# mobo_v2_0_6-20-18-mobo-only.net
KiCad netlist of a schematic drawn in EAGLE
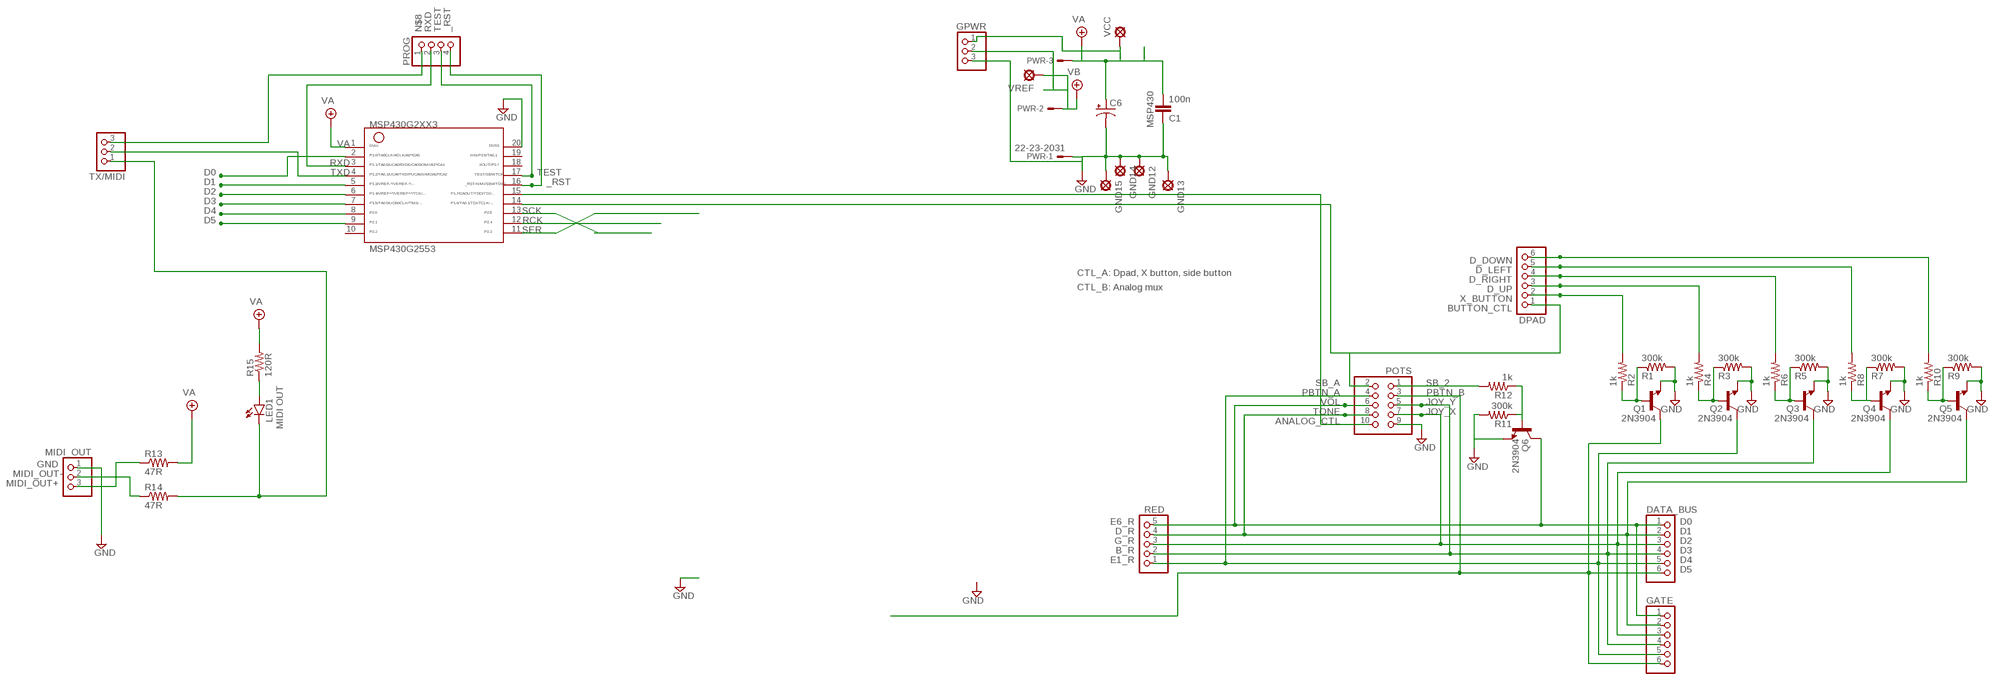
[diagram p0: schematic, sheet 1]

(export (version "E")
  (design (tool "Eeschema 10.0.6"))
  (components
    (comp (ref "C1")
      (value "100n")
      (footprint "eagle-import:050X030_050_3")
      (libsource (lib "eagle-import") (part "050X030_050"))
    )
    (comp (ref "C6")
      (value "0501")
      (footprint "eagle-import:050_020_1")
      (libsource (lib "eagle-import") (part "0501"))
    )
    (comp (ref "DATA_BUS")
      (value "PINHD-1X6")
      (footprint "eagle-import:1X06")
      (libsource (lib "eagle-import") (part "PINHD-1X6"))
    )
    (comp (ref "DPAD")
      (value "PINHD-1X6")
      (footprint "eagle-import:1X06")
      (libsource (lib "eagle-import") (part "PINHD-1X6"))
    )
    (comp (ref "GATE")
      (value "PINHD-1X6")
      (footprint "eagle-import:1X06")
      (libsource (lib "eagle-import") (part "PINHD-1X6"))
    )
    (comp (ref "GND12")
      (value "PAD")
      (footprint "eagle-import:SQUARE")
      (libsource (lib "eagle-import") (part "PAD"))
    )
    (comp (ref "GND13")
      (value "PAD")
      (footprint "eagle-import:SQUARE")
      (libsource (lib "eagle-import") (part "PAD"))
    )
    (comp (ref "GND14")
      (value "PAD")
      (footprint "eagle-import:SQUARE")
      (libsource (lib "eagle-import") (part "PAD"))
    )
    (comp (ref "GND15")
      (value "PAD")
      (footprint "eagle-import:SQUARE")
      (libsource (lib "eagle-import") (part "PAD"))
    )
    (comp (ref "GPWR")
      (value "PINHD-1X3")
      (footprint "eagle-import:1X03")
      (libsource (lib "eagle-import") (part "PINHD-1X3"))
    )
    (comp (ref "LED1")
      (value "LED3MM")
      (footprint "eagle-import:LED3MM")
      (libsource (lib "eagle-import") (part "LED3MM"))
    )
    (comp (ref "MIDI_OUT")
      (value "PINHD-1X3")
      (footprint "eagle-import:1X03")
      (libsource (lib "eagle-import") (part "PINHD-1X3"))
    )
    (comp (ref "MSP430G2553")
      (value "G2XX3---N20")
      (footprint "eagle-import:N20")
      (libsource (lib "eagle-import") (part "G2XX3---N20"))
    )
    (comp (ref "POTS")
      (value "PINHD-2X5IDC")
      (footprint "eagle-import:10PIN_IDC")
      (libsource (lib "eagle-import") (part "PINHD-2X5IDC"))
    )
    (comp (ref "PROG")
      (value "PINHD-1X4")
      (footprint "eagle-import:1X04")
      (libsource (lib "eagle-import") (part "PINHD-1X4"))
    )
    (comp (ref "PWR")
      (value "22-23-2031")
      (footprint "eagle-import:22-23-2031")
      (fields (field (name "MF") "MOLEX"))
      (libsource (lib "eagle-import") (part "22-23-2031"))
    )
    (comp (ref "Q1")
      (value "2N3904")
      (footprint "eagle-import:TO92-")
      (libsource (lib "eagle-import") (part "2N3904"))
    )
    (comp (ref "Q2")
      (value "2N3904")
      (footprint "eagle-import:TO92-")
      (libsource (lib "eagle-import") (part "2N3904"))
    )
    (comp (ref "Q3")
      (value "2N3904")
      (footprint "eagle-import:TO92-")
      (libsource (lib "eagle-import") (part "2N3904"))
    )
    (comp (ref "Q4")
      (value "2N3904")
      (footprint "eagle-import:TO92-")
      (libsource (lib "eagle-import") (part "2N3904"))
    )
    (comp (ref "Q5")
      (value "2N3904")
      (footprint "eagle-import:TO92-")
      (libsource (lib "eagle-import") (part "2N3904"))
    )
    (comp (ref "Q6")
      (value "2N3904")
      (footprint "eagle-import:TO92-")
      (libsource (lib "eagle-import") (part "2N3904"))
    )
    (comp (ref "R1")
      (value "300k")
      (footprint "eagle-import:R0207_3")
      (libsource (lib "eagle-import") (part "6MM.3"))
    )
    (comp (ref "R2")
      (value "1k")
      (footprint "eagle-import:R0207_3")
      (libsource (lib "eagle-import") (part "6MM.3"))
    )
    (comp (ref "R3")
      (value "300k")
      (footprint "eagle-import:R0207_3")
      (libsource (lib "eagle-import") (part "6MM.3"))
    )
    (comp (ref "R4")
      (value "1k")
      (footprint "eagle-import:R0207_3")
      (libsource (lib "eagle-import") (part "6MM.3"))
    )
    (comp (ref "R5")
      (value "300k")
      (footprint "eagle-import:R0207_3")
      (libsource (lib "eagle-import") (part "6MM.3"))
    )
    (comp (ref "R6")
      (value "1k")
      (footprint "eagle-import:R0207_3")
      (libsource (lib "eagle-import") (part "6MM.3"))
    )
    (comp (ref "R7")
      (value "300k")
      (footprint "eagle-import:R0207_3")
      (libsource (lib "eagle-import") (part "6MM.3"))
    )
    (comp (ref "R8")
      (value "1k")
      (footprint "eagle-import:R0207_3")
      (libsource (lib "eagle-import") (part "6MM.3"))
    )
    (comp (ref "R9")
      (value "300k")
      (footprint "eagle-import:R0207_3")
      (libsource (lib "eagle-import") (part "6MM.3"))
    )
    (comp (ref "R10")
      (value "1k")
      (footprint "eagle-import:R0207_3")
      (libsource (lib "eagle-import") (part "6MM.3"))
    )
    (comp (ref "R11")
      (value "300k")
      (footprint "eagle-import:R0207_3")
      (libsource (lib "eagle-import") (part "6MM.3"))
    )
    (comp (ref "R12")
      (value "1k")
      (footprint "eagle-import:R0207_3")
      (libsource (lib "eagle-import") (part "6MM.3"))
    )
    (comp (ref "R13")
      (value "47R")
      (footprint "eagle-import:R0207_3")
      (libsource (lib "eagle-import") (part "6MM.3"))
    )
    (comp (ref "R14")
      (value "47R")
      (footprint "eagle-import:R0207_3")
      (libsource (lib "eagle-import") (part "6MM.3"))
    )
    (comp (ref "R15")
      (value "120R")
      (footprint "eagle-import:R0207_3")
      (libsource (lib "eagle-import") (part "6MM.3"))
    )
    (comp (ref "RED")
      (value "PINHD-1X5")
      (footprint "eagle-import:1X05")
      (libsource (lib "eagle-import") (part "PINHD-1X5"))
    )
    (comp (ref "TX/MIDI")
      (value "PINHD-1X3")
      (footprint "eagle-import:1X03")
      (libsource (lib "eagle-import") (part "PINHD-1X3"))
    )
    (comp (ref "VCC")
      (value "PAD")
      (footprint "eagle-import:SQUARE")
      (libsource (lib "eagle-import") (part "PAD"))
    )
    (comp (ref "VREF")
      (value "PAD")
      (footprint "eagle-import:SQUARE")
      (libsource (lib "eagle-import") (part "PAD"))
    )
  )
  (nets
    (net (code "1") (name "/ANALOG_CTL") (class "Default")
      (node (ref "MSP430G2553") (pin "15") (pinfunction "15_15") (pintype "bidirectional"))
      (node (ref "POTS") (pin "10") (pinfunction "10_10") (pintype "passive"))
    )
    (net (code "2") (name "/BUTTON_CTL") (class "Default")
      (node (ref "DPAD") (pin "1") (pinfunction "1_1") (pintype "passive"))
      (node (ref "MSP430G2553") (pin "14") (pinfunction "14_14") (pintype "bidirectional"))
      (node (ref "POTS") (pin "2") (pinfunction "2_2") (pintype "passive"))
    )
    (net (code "3") (name "/D0") (class "Default")
      (node (ref "DATA_BUS") (pin "1") (pinfunction "1_1") (pintype "passive"))
      (node (ref "GATE") (pin "1") (pinfunction "1_1") (pintype "passive"))
      (node (ref "MSP430G2553") (pin "2") (pinfunction "2_2") (pintype "bidirectional"))
      (node (ref "POTS") (pin "6") (pinfunction "6_6") (pintype "passive"))
      (node (ref "Q6") (pin "1") (pinfunction "C_1") (pintype "passive"))
      (node (ref "RED") (pin "5") (pinfunction "5_5") (pintype "passive"))
    )
    (net (code "4") (name "/D1") (class "Default")
      (node (ref "DATA_BUS") (pin "2") (pinfunction "2_2") (pintype "passive"))
      (node (ref "GATE") (pin "2") (pinfunction "2_2") (pintype "passive"))
      (node (ref "MSP430G2553") (pin "5") (pinfunction "5_5") (pintype "bidirectional"))
      (node (ref "POTS") (pin "8") (pinfunction "8_8") (pintype "passive"))
      (node (ref "Q5") (pin "1") (pinfunction "C_1") (pintype "passive"))
      (node (ref "RED") (pin "4") (pinfunction "4_4") (pintype "passive"))
    )
    (net (code "5") (name "/D2") (class "Default")
      (node (ref "DATA_BUS") (pin "3") (pinfunction "3_3") (pintype "passive"))
      (node (ref "GATE") (pin "3") (pinfunction "3_3") (pintype "passive"))
      (node (ref "MSP430G2553") (pin "6") (pinfunction "6_6") (pintype "bidirectional"))
      (node (ref "POTS") (pin "7") (pinfunction "7_7") (pintype "passive"))
      (node (ref "Q4") (pin "1") (pinfunction "C_1") (pintype "passive"))
      (node (ref "RED") (pin "3") (pinfunction "3_3") (pintype "passive"))
    )
    (net (code "6") (name "/D3") (class "Default")
      (node (ref "DATA_BUS") (pin "4") (pinfunction "4_4") (pintype "passive"))
      (node (ref "GATE") (pin "4") (pinfunction "4_4") (pintype "passive"))
      (node (ref "MSP430G2553") (pin "7") (pinfunction "7_7") (pintype "bidirectional"))
      (node (ref "POTS") (pin "5") (pinfunction "5_5") (pintype "passive"))
      (node (ref "Q3") (pin "1") (pinfunction "C_1") (pintype "passive"))
      (node (ref "RED") (pin "2") (pinfunction "2_2") (pintype "passive"))
    )
    (net (code "7") (name "/D4") (class "Default")
      (node (ref "DATA_BUS") (pin "5") (pinfunction "5_5") (pintype "passive"))
      (node (ref "GATE") (pin "5") (pinfunction "5_5") (pintype "passive"))
      (node (ref "MSP430G2553") (pin "8") (pinfunction "8_8") (pintype "bidirectional"))
      (node (ref "POTS") (pin "4") (pinfunction "4_4") (pintype "passive"))
      (node (ref "Q2") (pin "1") (pinfunction "C_1") (pintype "passive"))
      (node (ref "RED") (pin "1") (pinfunction "1_1") (pintype "passive"))
    )
    (net (code "8") (name "/D5") (class "Default")
      (node (ref "DATA_BUS") (pin "6") (pinfunction "6_6") (pintype "passive"))
      (node (ref "GATE") (pin "6") (pinfunction "6_6") (pintype "passive"))
      (node (ref "MSP430G2553") (pin "9") (pinfunction "9_9") (pintype "bidirectional"))
      (node (ref "POTS") (pin "3") (pinfunction "3_3") (pintype "passive"))
      (node (ref "Q1") (pin "1") (pinfunction "C_1") (pintype "passive"))
    )
    (net (code "9") (name "/D_DOWN") (class "Default")
      (node (ref "DPAD") (pin "6") (pinfunction "6_6") (pintype "passive"))
      (node (ref "R10") (pin "2") (pinfunction "2_2") (pintype "passive"))
    )
    (net (code "10") (name "/D_LEFT") (class "Default")
      (node (ref "DPAD") (pin "5") (pinfunction "5_5") (pintype "passive"))
      (node (ref "R8") (pin "2") (pinfunction "2_2") (pintype "passive"))
    )
    (net (code "11") (name "/D_RIGHT") (class "Default")
      (node (ref "DPAD") (pin "4") (pinfunction "4_4") (pintype "passive"))
      (node (ref "R6") (pin "2") (pinfunction "2_2") (pintype "passive"))
    )
    (net (code "12") (name "/D_UP") (class "Default")
      (node (ref "DPAD") (pin "3") (pinfunction "3_3") (pintype "passive"))
      (node (ref "R4") (pin "2") (pinfunction "2_2") (pintype "passive"))
    )
    (net (code "13") (name "/MIDI_OUT+") (class "Default")
      (node (ref "MIDI_OUT") (pin "3") (pinfunction "3_3") (pintype "passive"))
      (node (ref "R13") (pin "1") (pinfunction "1_1") (pintype "passive"))
    )
    (net (code "14") (name "/MIDI_OUT-") (class "Default")
      (node (ref "MIDI_OUT") (pin "2") (pinfunction "2_2") (pintype "passive"))
      (node (ref "R14") (pin "1") (pinfunction "1_1") (pintype "passive"))
    )
    (net (code "15") (name "/N$8") (class "Default")
      (node (ref "PROG") (pin "1") (pinfunction "1_1") (pintype "passive"))
      (node (ref "TX/MIDI") (pin "3") (pinfunction "3_3") (pintype "passive"))
    )
    (net (code "16") (name "/RCK") (class "Default")
      (node (ref "MSP430G2553") (pin "12") (pinfunction "12_12") (pintype "bidirectional"))
    )
    (net (code "17") (name "/RXD") (class "Default")
      (node (ref "MSP430G2553") (pin "3") (pinfunction "3_3") (pintype "bidirectional"))
      (node (ref "PROG") (pin "2") (pinfunction "2_2") (pintype "passive"))
    )
    (net (code "18") (name "/SB_2") (class "Default")
      (node (ref "POTS") (pin "1") (pinfunction "1_1") (pintype "passive"))
      (node (ref "R12") (pin "2") (pinfunction "2_2") (pintype "passive"))
    )
    (net (code "19") (name "/SCK") (class "Default")
      (node (ref "MSP430G2553") (pin "13") (pinfunction "13_13") (pintype "bidirectional"))
    )
    (net (code "20") (name "/SER") (class "Default")
      (node (ref "MSP430G2553") (pin "11") (pinfunction "11_11") (pintype "bidirectional"))
    )
    (net (code "21") (name "/TEST") (class "Default")
      (node (ref "MSP430G2553") (pin "17") (pinfunction "17_17") (pintype "bidirectional"))
      (node (ref "PROG") (pin "3") (pinfunction "3_3") (pintype "passive"))
    )
    (net (code "22") (name "/TXD") (class "Default")
      (node (ref "MSP430G2553") (pin "4") (pinfunction "4_4") (pintype "bidirectional"))
      (node (ref "TX/MIDI") (pin "2") (pinfunction "2_2") (pintype "passive"))
    )
    (net (code "23") (name "/X_BUTTON") (class "Default")
      (node (ref "DPAD") (pin "2") (pinfunction "2_2") (pintype "passive"))
      (node (ref "R2") (pin "2") (pinfunction "2_2") (pintype "passive"))
    )
    (net (code "24") (name "/_RST") (class "Default")
      (node (ref "MSP430G2553") (pin "16") (pinfunction "16_16") (pintype "bidirectional"))
      (node (ref "PROG") (pin "4") (pinfunction "4_4") (pintype "passive"))
    )
    (net (code "25") (name "GND") (class "Default")
      (node (ref "C1") (pin "1") (pinfunction "1_1") (pintype "passive"))
      (node (ref "C6") (pin "-") (pinfunction "-_-") (pintype "passive"))
      (node (ref "GND12") (pin "1") (pinfunction "PAD_1") (pintype "passive"))
      (node (ref "GND13") (pin "1") (pinfunction "PAD_1") (pintype "passive"))
      (node (ref "GND14") (pin "1") (pinfunction "PAD_1") (pintype "passive"))
      (node (ref "GND15") (pin "1") (pinfunction "PAD_1") (pintype "passive"))
      (node (ref "GPWR") (pin "3") (pinfunction "3_3") (pintype "passive"))
      (node (ref "MIDI_OUT") (pin "1") (pinfunction "1_1") (pintype "passive"))
      (node (ref "MSP430G2553") (pin "20") (pinfunction "20_20") (pintype "bidirectional"))
      (node (ref "POTS") (pin "9") (pinfunction "9_9") (pintype "passive"))
      (node (ref "PWR") (pin "1") (pinfunction "S_1") (pintype "passive"))
      (node (ref "Q1") (pin "3") (pinfunction "E_3") (pintype "passive"))
      (node (ref "Q2") (pin "3") (pinfunction "E_3") (pintype "passive"))
      (node (ref "Q3") (pin "3") (pinfunction "E_3") (pintype "passive"))
      (node (ref "Q4") (pin "3") (pinfunction "E_3") (pintype "passive"))
      (node (ref "Q5") (pin "3") (pinfunction "E_3") (pintype "passive"))
      (node (ref "Q6") (pin "3") (pinfunction "E_3") (pintype "passive"))
      (node (ref "R1") (pin "2") (pinfunction "2_2") (pintype "passive"))
      (node (ref "R11") (pin "2") (pinfunction "2_2") (pintype "passive"))
      (node (ref "R3") (pin "2") (pinfunction "2_2") (pintype "passive"))
      (node (ref "R5") (pin "2") (pinfunction "2_2") (pintype "passive"))
      (node (ref "R7") (pin "2") (pinfunction "2_2") (pintype "passive"))
      (node (ref "R9") (pin "2") (pinfunction "2_2") (pintype "passive"))
    )
    (net (code "26") (name "Net-(LED1-C)") (class "Default")
      (node (ref "LED1") (pin "K") (pinfunction "C_K") (pintype "passive"))
      (node (ref "R14") (pin "2") (pinfunction "2_2") (pintype "passive"))
      (node (ref "TX/MIDI") (pin "1") (pinfunction "1_1") (pintype "passive"))
    )
    (net (code "27") (name "Net-(LED1-PadA)") (class "Default")
      (node (ref "LED1") (pin "A") (pinfunction "A_A") (pintype "passive"))
      (node (ref "R15") (pin "1") (pinfunction "1_1") (pintype "passive"))
    )
    (net (code "28") (name "Net-(Q1-B)") (class "Default")
      (node (ref "Q1") (pin "2") (pinfunction "B_2") (pintype "passive"))
      (node (ref "R1") (pin "1") (pinfunction "1_1") (pintype "passive"))
      (node (ref "R2") (pin "1") (pinfunction "1_1") (pintype "passive"))
    )
    (net (code "29") (name "Net-(Q2-B)") (class "Default")
      (node (ref "Q2") (pin "2") (pinfunction "B_2") (pintype "passive"))
      (node (ref "R3") (pin "1") (pinfunction "1_1") (pintype "passive"))
      (node (ref "R4") (pin "1") (pinfunction "1_1") (pintype "passive"))
    )
    (net (code "30") (name "Net-(Q3-B)") (class "Default")
      (node (ref "Q3") (pin "2") (pinfunction "B_2") (pintype "passive"))
      (node (ref "R5") (pin "1") (pinfunction "1_1") (pintype "passive"))
      (node (ref "R6") (pin "1") (pinfunction "1_1") (pintype "passive"))
    )
    (net (code "31") (name "Net-(Q4-B)") (class "Default")
      (node (ref "Q4") (pin "2") (pinfunction "B_2") (pintype "passive"))
      (node (ref "R7") (pin "1") (pinfunction "1_1") (pintype "passive"))
      (node (ref "R8") (pin "1") (pinfunction "1_1") (pintype "passive"))
    )
    (net (code "32") (name "Net-(Q5-B)") (class "Default")
      (node (ref "Q5") (pin "2") (pinfunction "B_2") (pintype "passive"))
      (node (ref "R10") (pin "1") (pinfunction "1_1") (pintype "passive"))
      (node (ref "R9") (pin "1") (pinfunction "1_1") (pintype "passive"))
    )
    (net (code "33") (name "Net-(Q6-B)") (class "Default")
      (node (ref "Q6") (pin "2") (pinfunction "B_2") (pintype "passive"))
      (node (ref "R11") (pin "1") (pinfunction "1_1") (pintype "passive"))
      (node (ref "R12") (pin "1") (pinfunction "1_1") (pintype "passive"))
    )
    (net (code "34") (name "VA") (class "Default")
      (node (ref "C1") (pin "2") (pinfunction "2_2") (pintype "passive"))
      (node (ref "C6") (pin "+") (pinfunction "+_+") (pintype "passive"))
      (node (ref "GPWR") (pin "1") (pinfunction "1_1") (pintype "passive"))
      (node (ref "MSP430G2553") (pin "1") (pinfunction "1_1") (pintype "bidirectional"))
      (node (ref "PWR") (pin "3") (pinfunction "S_3") (pintype "passive"))
      (node (ref "R13") (pin "2") (pinfunction "2_2") (pintype "passive"))
      (node (ref "R15") (pin "2") (pinfunction "2_2") (pintype "passive"))
      (node (ref "VCC") (pin "1") (pinfunction "PAD_1") (pintype "passive"))
    )
    (net (code "35") (name "VB") (class "Default")
      (node (ref "GPWR") (pin "2") (pinfunction "2_2") (pintype "passive"))
      (node (ref "PWR") (pin "2") (pinfunction "S_2") (pintype "passive"))
      (node (ref "VREF") (pin "1") (pinfunction "PAD_1") (pintype "passive"))
    )
    (net (code "36") (name "unconnected-(MSP430G2553-Pad10)") (class "Default")
      (node (ref "MSP430G2553") (pin "10") (pinfunction "10_10") (pintype "bidirectional"))
    )
    (net (code "37") (name "unconnected-(MSP430G2553-Pad18)") (class "Default")
      (node (ref "MSP430G2553") (pin "18") (pinfunction "18_18") (pintype "bidirectional"))
    )
    (net (code "38") (name "unconnected-(MSP430G2553-Pad19)") (class "Default")
      (node (ref "MSP430G2553") (pin "19") (pinfunction "19_19") (pintype "bidirectional"))
    )
  )
)
